# relay.net
KiCad netlist of a schematic drawn in Altium Designer
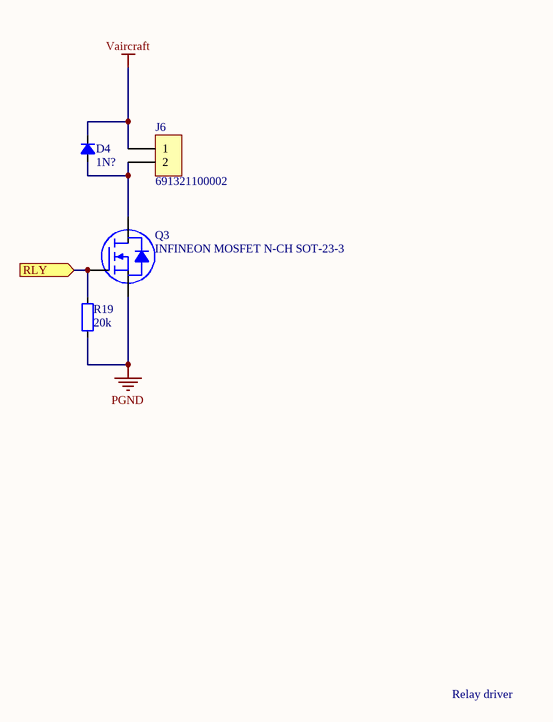
[diagram p0: relay.SchDoc]

(export (version "E")
  (design (tool "Eeschema 10.0.6"))
  (components
    (comp (ref "D4")
      (value "1N?")
      (footprint "Diodes:SOD123F")
      (description "Diode")
      (fields (field (name "Comment") "Diode_SOD523"))
      (libsource (lib "SCH_Active") (part "Diode_SOD523"))
    )
    (comp (ref "J6")
      (value "691321100002")
      (footprint "691322110002")
      (description "WR-TBL Terminal block - serie 3211 - 3.50 mm")
      (fields
        (field (name "MANUFACTURER") "Würth Elektronik eiSos GmbH")
        (field (name "CREATED BY") "Karrer Zheng")
      )
      (libsource (lib "ALTIUM-TBL_3_50_3211_VERTICAL_PCB_HEADER_69132110000X-rev15c") (part "691321100002"))
    )
    (comp (ref "Q3")
      (value "INFINEON MOSFET N-CH SOT-23-3")
      (footprint "INFINEON SOT-23-3")
      (libsource (lib "N-CH FETs") (part "INFINEON MOSFET N-CH SOT-23-3"))
    )
    (comp (ref "R19")
      (value "20k")
      (footprint "PCB_PassiveRes:RES_0603")
      (description "Resistor")
      (fields (field (name "Comment") "Res_0603"))
      (libsource (lib "SCH_Passive") (part "Res_0603"))
    )
  )
  (nets
    (net (code "1") (name "/RLY") (class "Default")
      (node (ref "Q3") (pin "1") (pinfunction "G_1") (pintype "passive"))
      (node (ref "R19") (pin "2") (pinfunction "2_2") (pintype "passive"))
    )
    (net (code "2") (name "Net-(D4-A)") (class "Default")
      (node (ref "D4") (pin "1") (pinfunction "A_1") (pintype "passive"))
      (node (ref "J6") (pin "2") (pinfunction "2_2") (pintype "passive"))
      (node (ref "Q3") (pin "2") (pinfunction "D_2") (pintype "passive"))
    )
    (net (code "3") (name "PGND") (class "Default")
      (node (ref "Q3") (pin "3") (pinfunction "S_3") (pintype "passive"))
      (node (ref "R19") (pin "1") (pinfunction "1_1") (pintype "passive"))
    )
    (net (code "4") (name "Vaircraft") (class "Default")
      (node (ref "D4") (pin "2") (pinfunction "K_2") (pintype "passive"))
      (node (ref "J6") (pin "1") (pinfunction "1_1") (pintype "passive"))
    )
  )
)
